# Arduino_Ibus.net
KiCad netlist of a schematic drawn in EAGLE
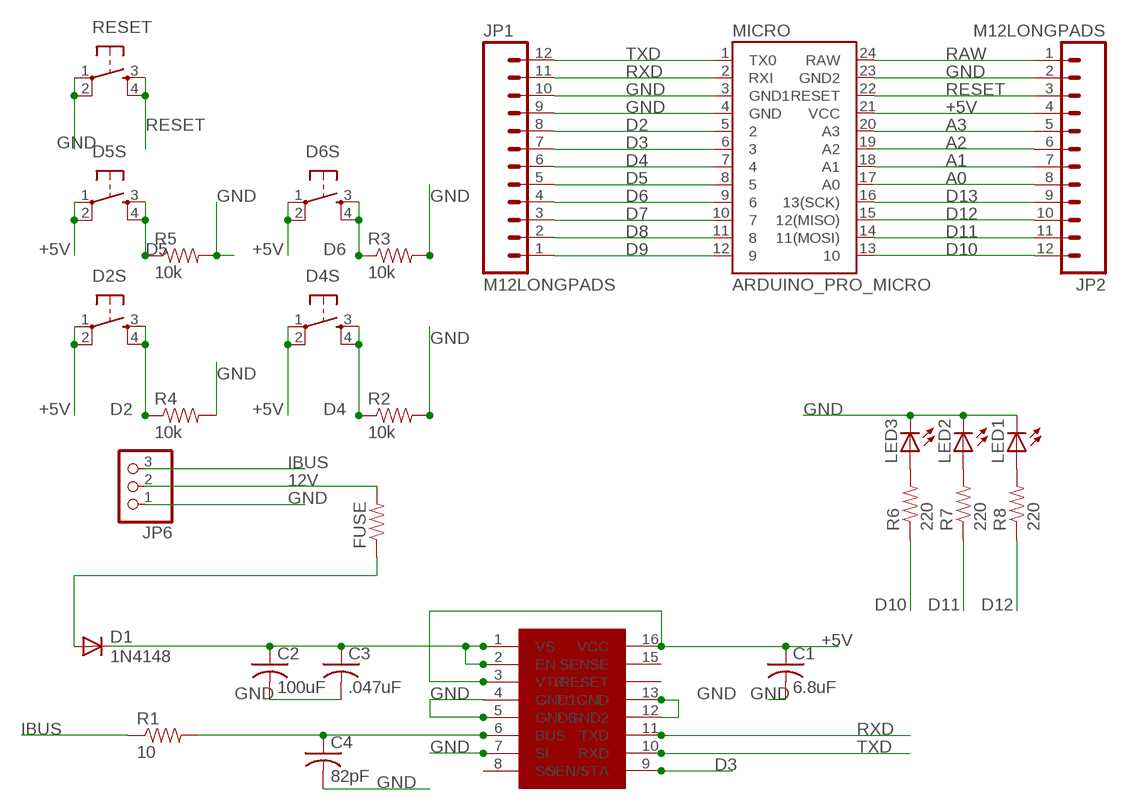
[diagram p0: schematic, sheet 1]

(export (version "E")
  (design (tool "Eeschema 10.0.6"))
  (components
    (comp (ref "C1")
      (value "6.8uF")
      (footprint "eagle-import:C1206")
      (libsource (lib "eagle-import") (part "C-USC1206"))
    )
    (comp (ref "C2")
      (value "100uF")
      (footprint "eagle-import:C1206")
      (libsource (lib "eagle-import") (part "C-USC1206"))
    )
    (comp (ref "C3")
      (value ".047uF")
      (footprint "eagle-import:C1206")
      (libsource (lib "eagle-import") (part "C-USC1206"))
    )
    (comp (ref "C4")
      (value "82pF")
      (footprint "eagle-import:C1206")
      (libsource (lib "eagle-import") (part "C-USC1206"))
    )
    (comp (ref "D1")
      (value "1N4148")
      (footprint "eagle-import:SMA-DIODE")
      (libsource (lib "eagle-import") (part "DIODESMA"))
    )
    (comp (ref "D2S")
      (value "TAC_SWITCHPTH")
      (footprint "eagle-import:TACTILE-PTH")
      (libsource (lib "eagle-import") (part "TAC_SWITCHPTH"))
    )
    (comp (ref "D4S")
      (value "TAC_SWITCHPTH")
      (footprint "eagle-import:TACTILE-PTH")
      (libsource (lib "eagle-import") (part "TAC_SWITCHPTH"))
    )
    (comp (ref "D5S")
      (value "TAC_SWITCHPTH")
      (footprint "eagle-import:TACTILE-PTH")
      (libsource (lib "eagle-import") (part "TAC_SWITCHPTH"))
    )
    (comp (ref "D6S")
      (value "TAC_SWITCHPTH")
      (footprint "eagle-import:TACTILE-PTH")
      (libsource (lib "eagle-import") (part "TAC_SWITCHPTH"))
    )
    (comp (ref "FUSE")
      (value "RESISTOR1206")
      (footprint "eagle-import:1206")
      (libsource (lib "eagle-import") (part "RESISTOR1206"))
    )
    (comp (ref "JP1")
      (value "M12LONGPADS")
      (footprint "eagle-import:1X12_LONGPADS")
      (libsource (lib "eagle-import") (part "M12LONGPADS"))
    )
    (comp (ref "JP2")
      (value "M12LONGPADS")
      (footprint "eagle-import:1X12_LONGPADS")
      (libsource (lib "eagle-import") (part "M12LONGPADS"))
    )
    (comp (ref "JP6")
      (value "PINHD-1X3")
      (footprint "eagle-import:1X03")
      (libsource (lib "eagle-import") (part "PINHD-1X3"))
    )
    (comp (ref "LED1")
      (value "LED1206")
      (footprint "eagle-import:LED-1206")
      (libsource (lib "eagle-import") (part "LED1206"))
    )
    (comp (ref "LED2")
      (value "LED1206")
      (footprint "eagle-import:LED-1206")
      (libsource (lib "eagle-import") (part "LED1206"))
    )
    (comp (ref "LED3")
      (value "LED1206")
      (footprint "eagle-import:LED-1206")
      (libsource (lib "eagle-import") (part "LED1206"))
    )
    (comp (ref "MICRO")
      (value "ARDUINO_PRO_MICRO")
      (footprint "eagle-import:ARDUINO_PRO_MICRO")
      (libsource (lib "eagle-import") (part "ARDUINO_PRO_MICRO"))
    )
    (comp (ref "R1")
      (value "10")
      (footprint "eagle-import:1206")
      (libsource (lib "eagle-import") (part "RESISTOR1206"))
    )
    (comp (ref "R2")
      (value "10k")
      (footprint "eagle-import:1206")
      (libsource (lib "eagle-import") (part "RESISTOR1206"))
    )
    (comp (ref "R3")
      (value "10k")
      (footprint "eagle-import:1206")
      (libsource (lib "eagle-import") (part "RESISTOR1206"))
    )
    (comp (ref "R4")
      (value "10k")
      (footprint "eagle-import:1206")
      (libsource (lib "eagle-import") (part "RESISTOR1206"))
    )
    (comp (ref "R5")
      (value "10k")
      (footprint "eagle-import:1206")
      (libsource (lib "eagle-import") (part "RESISTOR1206"))
    )
    (comp (ref "R6")
      (value "220")
      (footprint "eagle-import:1206")
      (libsource (lib "eagle-import") (part "RESISTOR1206"))
    )
    (comp (ref "R7")
      (value "220")
      (footprint "eagle-import:1206")
      (libsource (lib "eagle-import") (part "RESISTOR1206"))
    )
    (comp (ref "R8")
      (value "220")
      (footprint "eagle-import:1206")
      (libsource (lib "eagle-import") (part "RESISTOR1206"))
    )
    (comp (ref "RESET")
      (value "TAC_SWITCHPTH")
      (footprint "eagle-import:TACTILE-PTH")
      (libsource (lib "eagle-import") (part "TAC_SWITCHPTH"))
    )
    (comp (ref "U$1")
      (value "TH3122")
      (footprint "eagle-import:SO16W")
      (libsource (lib "eagle-import") (part "TH3122"))
    )
  )
  (nets
    (net (code "1") (name "/+5V") (class "Default")
      (node (ref "C1") (pin "1") (pinfunction "1_1") (pintype "passive"))
      (node (ref "D2S") (pin "1") (pinfunction "1_1") (pintype "passive"))
      (node (ref "D2S") (pin "2") (pinfunction "2_2") (pintype "passive"))
      (node (ref "D4S") (pin "1") (pinfunction "1_1") (pintype "passive"))
      (node (ref "D4S") (pin "2") (pinfunction "2_2") (pintype "passive"))
      (node (ref "D5S") (pin "1") (pinfunction "1_1") (pintype "passive"))
      (node (ref "D5S") (pin "2") (pinfunction "2_2") (pintype "passive"))
      (node (ref "D6S") (pin "1") (pinfunction "1_1") (pintype "passive"))
      (node (ref "D6S") (pin "2") (pinfunction "2_2") (pintype "passive"))
      (node (ref "JP2") (pin "4") (pinfunction "4_4") (pintype "passive"))
      (node (ref "MICRO") (pin "21") (pinfunction "VCC_21") (pintype "bidirectional"))
      (node (ref "U$1") (pin "16") (pinfunction "VCC_16") (pintype "power_in"))
      (node (ref "U$1") (pin "3") (pinfunction "VTR_3") (pintype "bidirectional"))
    )
    (net (code "2") (name "/12V") (class "Default")
      (node (ref "FUSE") (pin "2") (pinfunction "2_2") (pintype "passive"))
      (node (ref "JP6") (pin "2") (pinfunction "2_2") (pintype "passive"))
    )
    (net (code "3") (name "/A0") (class "Default")
      (node (ref "JP2") (pin "8") (pinfunction "8_8") (pintype "passive"))
      (node (ref "MICRO") (pin "17") (pinfunction "A0_17") (pintype "bidirectional"))
    )
    (net (code "4") (name "/A1") (class "Default")
      (node (ref "JP2") (pin "7") (pinfunction "7_7") (pintype "passive"))
      (node (ref "MICRO") (pin "18") (pinfunction "A1_18") (pintype "bidirectional"))
    )
    (net (code "5") (name "/A2") (class "Default")
      (node (ref "JP2") (pin "6") (pinfunction "6_6") (pintype "passive"))
      (node (ref "MICRO") (pin "19") (pinfunction "A2_19") (pintype "bidirectional"))
    )
    (net (code "6") (name "/A3") (class "Default")
      (node (ref "JP2") (pin "5") (pinfunction "5_5") (pintype "passive"))
      (node (ref "MICRO") (pin "20") (pinfunction "A3_20") (pintype "bidirectional"))
    )
    (net (code "7") (name "/D2") (class "Default")
      (node (ref "D2S") (pin "3") (pinfunction "3_3") (pintype "passive"))
      (node (ref "D2S") (pin "4") (pinfunction "4_4") (pintype "passive"))
      (node (ref "JP1") (pin "8") (pinfunction "8_8") (pintype "passive"))
      (node (ref "MICRO") (pin "5") (pinfunction "2_5") (pintype "bidirectional"))
      (node (ref "R4") (pin "1") (pinfunction "1_1") (pintype "passive"))
    )
    (net (code "8") (name "/D3") (class "Default")
      (node (ref "JP1") (pin "7") (pinfunction "7_7") (pintype "passive"))
      (node (ref "MICRO") (pin "6") (pinfunction "3_6") (pintype "bidirectional"))
      (node (ref "U$1") (pin "9") (pinfunction "SEN/STA_9") (pintype "bidirectional"))
    )
    (net (code "9") (name "/D4") (class "Default")
      (node (ref "D4S") (pin "3") (pinfunction "3_3") (pintype "passive"))
      (node (ref "D4S") (pin "4") (pinfunction "4_4") (pintype "passive"))
      (node (ref "JP1") (pin "6") (pinfunction "6_6") (pintype "passive"))
      (node (ref "MICRO") (pin "7") (pinfunction "4_7") (pintype "bidirectional"))
      (node (ref "R2") (pin "1") (pinfunction "1_1") (pintype "passive"))
    )
    (net (code "10") (name "/D5") (class "Default")
      (node (ref "D5S") (pin "3") (pinfunction "3_3") (pintype "passive"))
      (node (ref "D5S") (pin "4") (pinfunction "4_4") (pintype "passive"))
      (node (ref "JP1") (pin "5") (pinfunction "5_5") (pintype "passive"))
      (node (ref "MICRO") (pin "8") (pinfunction "5_8") (pintype "bidirectional"))
      (node (ref "R5") (pin "1") (pinfunction "1_1") (pintype "passive"))
    )
    (net (code "11") (name "/D6") (class "Default")
      (node (ref "D6S") (pin "3") (pinfunction "3_3") (pintype "passive"))
      (node (ref "D6S") (pin "4") (pinfunction "4_4") (pintype "passive"))
      (node (ref "JP1") (pin "4") (pinfunction "4_4") (pintype "passive"))
      (node (ref "MICRO") (pin "9") (pinfunction "6_9") (pintype "bidirectional"))
      (node (ref "R3") (pin "1") (pinfunction "1_1") (pintype "passive"))
    )
    (net (code "12") (name "/D7") (class "Default")
      (node (ref "JP1") (pin "3") (pinfunction "3_3") (pintype "passive"))
      (node (ref "MICRO") (pin "10") (pinfunction "7_10") (pintype "bidirectional"))
    )
    (net (code "13") (name "/D8") (class "Default")
      (node (ref "JP1") (pin "2") (pinfunction "2_2") (pintype "passive"))
      (node (ref "MICRO") (pin "11") (pinfunction "8_11") (pintype "bidirectional"))
    )
    (net (code "14") (name "/D9") (class "Default")
      (node (ref "JP1") (pin "1") (pinfunction "1_1") (pintype "passive"))
      (node (ref "MICRO") (pin "12") (pinfunction "9_12") (pintype "bidirectional"))
    )
    (net (code "15") (name "/D10") (class "Default")
      (node (ref "JP2") (pin "12") (pinfunction "12_12") (pintype "passive"))
      (node (ref "MICRO") (pin "13") (pinfunction "10_13") (pintype "bidirectional"))
      (node (ref "R6") (pin "1") (pinfunction "1_1") (pintype "passive"))
    )
    (net (code "16") (name "/D11") (class "Default")
      (node (ref "JP2") (pin "11") (pinfunction "11_11") (pintype "passive"))
      (node (ref "MICRO") (pin "14") (pinfunction "11(MOSI)_14") (pintype "bidirectional"))
      (node (ref "R7") (pin "1") (pinfunction "1_1") (pintype "passive"))
    )
    (net (code "17") (name "/D12") (class "Default")
      (node (ref "JP2") (pin "10") (pinfunction "10_10") (pintype "passive"))
      (node (ref "MICRO") (pin "15") (pinfunction "12(MISO)_15") (pintype "bidirectional"))
      (node (ref "R8") (pin "1") (pinfunction "1_1") (pintype "passive"))
    )
    (net (code "18") (name "/D13") (class "Default")
      (node (ref "JP2") (pin "9") (pinfunction "9_9") (pintype "passive"))
      (node (ref "MICRO") (pin "16") (pinfunction "13(SCK)_16") (pintype "bidirectional"))
    )
    (net (code "19") (name "/GND") (class "Default")
      (node (ref "C1") (pin "2") (pinfunction "2_2") (pintype "passive"))
      (node (ref "C2") (pin "2") (pinfunction "2_2") (pintype "passive"))
      (node (ref "C3") (pin "2") (pinfunction "2_2") (pintype "passive"))
      (node (ref "C4") (pin "2") (pinfunction "2_2") (pintype "passive"))
      (node (ref "JP1") (pin "10") (pinfunction "10_10") (pintype "passive"))
      (node (ref "JP1") (pin "9") (pinfunction "9_9") (pintype "passive"))
      (node (ref "JP2") (pin "2") (pinfunction "2_2") (pintype "passive"))
      (node (ref "JP6") (pin "1") (pinfunction "1_1") (pintype "passive"))
      (node (ref "LED1") (pin "C") (pinfunction "C_C") (pintype "passive"))
      (node (ref "LED2") (pin "C") (pinfunction "C_C") (pintype "passive"))
      (node (ref "LED3") (pin "C") (pinfunction "C_C") (pintype "passive"))
      (node (ref "MICRO") (pin "23") (pinfunction "GND2_23") (pintype "bidirectional"))
      (node (ref "MICRO") (pin "3") (pinfunction "GND1_3") (pintype "bidirectional"))
      (node (ref "MICRO") (pin "4") (pinfunction "GND_4") (pintype "bidirectional"))
      (node (ref "R2") (pin "2") (pinfunction "2_2") (pintype "passive"))
      (node (ref "R3") (pin "2") (pinfunction "2_2") (pintype "passive"))
      (node (ref "R4") (pin "2") (pinfunction "2_2") (pintype "passive"))
      (node (ref "R5") (pin "2") (pinfunction "2_2") (pintype "passive"))
      (node (ref "RESET") (pin "1") (pinfunction "1_1") (pintype "passive"))
      (node (ref "RESET") (pin "2") (pinfunction "2_2") (pintype "passive"))
      (node (ref "U$1") (pin "12") (pinfunction "GND2_12") (pintype "power_in"))
      (node (ref "U$1") (pin "13") (pinfunction "GND_13") (pintype "power_in"))
      (node (ref "U$1") (pin "4") (pinfunction "GND1_4") (pintype "power_in"))
      (node (ref "U$1") (pin "5") (pinfunction "GND3_5") (pintype "power_in"))
      (node (ref "U$1") (pin "7") (pinfunction "SI_7") (pintype "bidirectional"))
    )
    (net (code "20") (name "/IBUS") (class "Default")
      (node (ref "JP6") (pin "3") (pinfunction "3_3") (pintype "passive"))
      (node (ref "R1") (pin "1") (pinfunction "1_1") (pintype "passive"))
    )
    (net (code "21") (name "/RAW") (class "Default")
      (node (ref "JP2") (pin "1") (pinfunction "1_1") (pintype "passive"))
      (node (ref "MICRO") (pin "24") (pinfunction "RAW_24") (pintype "bidirectional"))
    )
    (net (code "22") (name "/RESET") (class "Default")
      (node (ref "JP2") (pin "3") (pinfunction "3_3") (pintype "passive"))
      (node (ref "MICRO") (pin "22") (pinfunction "RESET_22") (pintype "bidirectional"))
      (node (ref "RESET") (pin "3") (pinfunction "3_3") (pintype "passive"))
      (node (ref "RESET") (pin "4") (pinfunction "4_4") (pintype "passive"))
    )
    (net (code "23") (name "/RXD") (class "Default")
      (node (ref "JP1") (pin "11") (pinfunction "11_11") (pintype "passive"))
      (node (ref "MICRO") (pin "2") (pinfunction "RXI_2") (pintype "bidirectional"))
      (node (ref "U$1") (pin "11") (pinfunction "TXD_11") (pintype "output"))
    )
    (net (code "24") (name "/TXD") (class "Default")
      (node (ref "JP1") (pin "12") (pinfunction "12_12") (pintype "passive"))
      (node (ref "MICRO") (pin "1") (pinfunction "TX0_1") (pintype "bidirectional"))
      (node (ref "U$1") (pin "10") (pinfunction "RXD_10") (pintype "input"))
    )
    (net (code "25") (name "Net-(D1-PadA)") (class "Default")
      (node (ref "D1") (pin "A") (pinfunction "A_A") (pintype "passive"))
      (node (ref "FUSE") (pin "1") (pinfunction "1_1") (pintype "passive"))
    )
    (net (code "26") (name "Net-(LED1-PadA)") (class "Default")
      (node (ref "LED1") (pin "A") (pinfunction "A_A") (pintype "passive"))
      (node (ref "R8") (pin "2") (pinfunction "2_2") (pintype "passive"))
    )
    (net (code "27") (name "Net-(LED2-PadA)") (class "Default")
      (node (ref "LED2") (pin "A") (pinfunction "A_A") (pintype "passive"))
      (node (ref "R7") (pin "2") (pinfunction "2_2") (pintype "passive"))
    )
    (net (code "28") (name "Net-(LED3-PadA)") (class "Default")
      (node (ref "LED3") (pin "A") (pinfunction "A_A") (pintype "passive"))
      (node (ref "R6") (pin "2") (pinfunction "2_2") (pintype "passive"))
    )
    (net (code "29") (name "Net-(U$1-BUS)") (class "Default")
      (node (ref "C4") (pin "1") (pinfunction "1_1") (pintype "passive"))
      (node (ref "R1") (pin "2") (pinfunction "2_2") (pintype "passive"))
      (node (ref "U$1") (pin "6") (pinfunction "BUS_6") (pintype "bidirectional"))
    )
    (net (code "30") (name "Net-(U$1-EN)") (class "Default")
      (node (ref "C2") (pin "1") (pinfunction "1_1") (pintype "passive"))
      (node (ref "C3") (pin "1") (pinfunction "1_1") (pintype "passive"))
      (node (ref "D1") (pin "C") (pinfunction "C_C") (pintype "passive"))
      (node (ref "U$1") (pin "1") (pinfunction "VS_1") (pintype "power_in"))
      (node (ref "U$1") (pin "2") (pinfunction "EN_2") (pintype "bidirectional"))
    )
    (net (code "31") (name "unconnected-(U$1-RESET-Pad14)") (class "Default")
      (node (ref "U$1") (pin "14") (pinfunction "RESET_14") (pintype "bidirectional"))
    )
    (net (code "32") (name "unconnected-(U$1-SENSE-Pad15)") (class "Default")
      (node (ref "U$1") (pin "15") (pinfunction "SENSE_15") (pintype "bidirectional"))
    )
    (net (code "33") (name "unconnected-(U$1-SO-Pad8)") (class "Default")
      (node (ref "U$1") (pin "8") (pinfunction "SO_8") (pintype "bidirectional"))
    )
  )
)
